# Power_Circuitry.net
KiCad netlist of a schematic drawn in Altium Designer
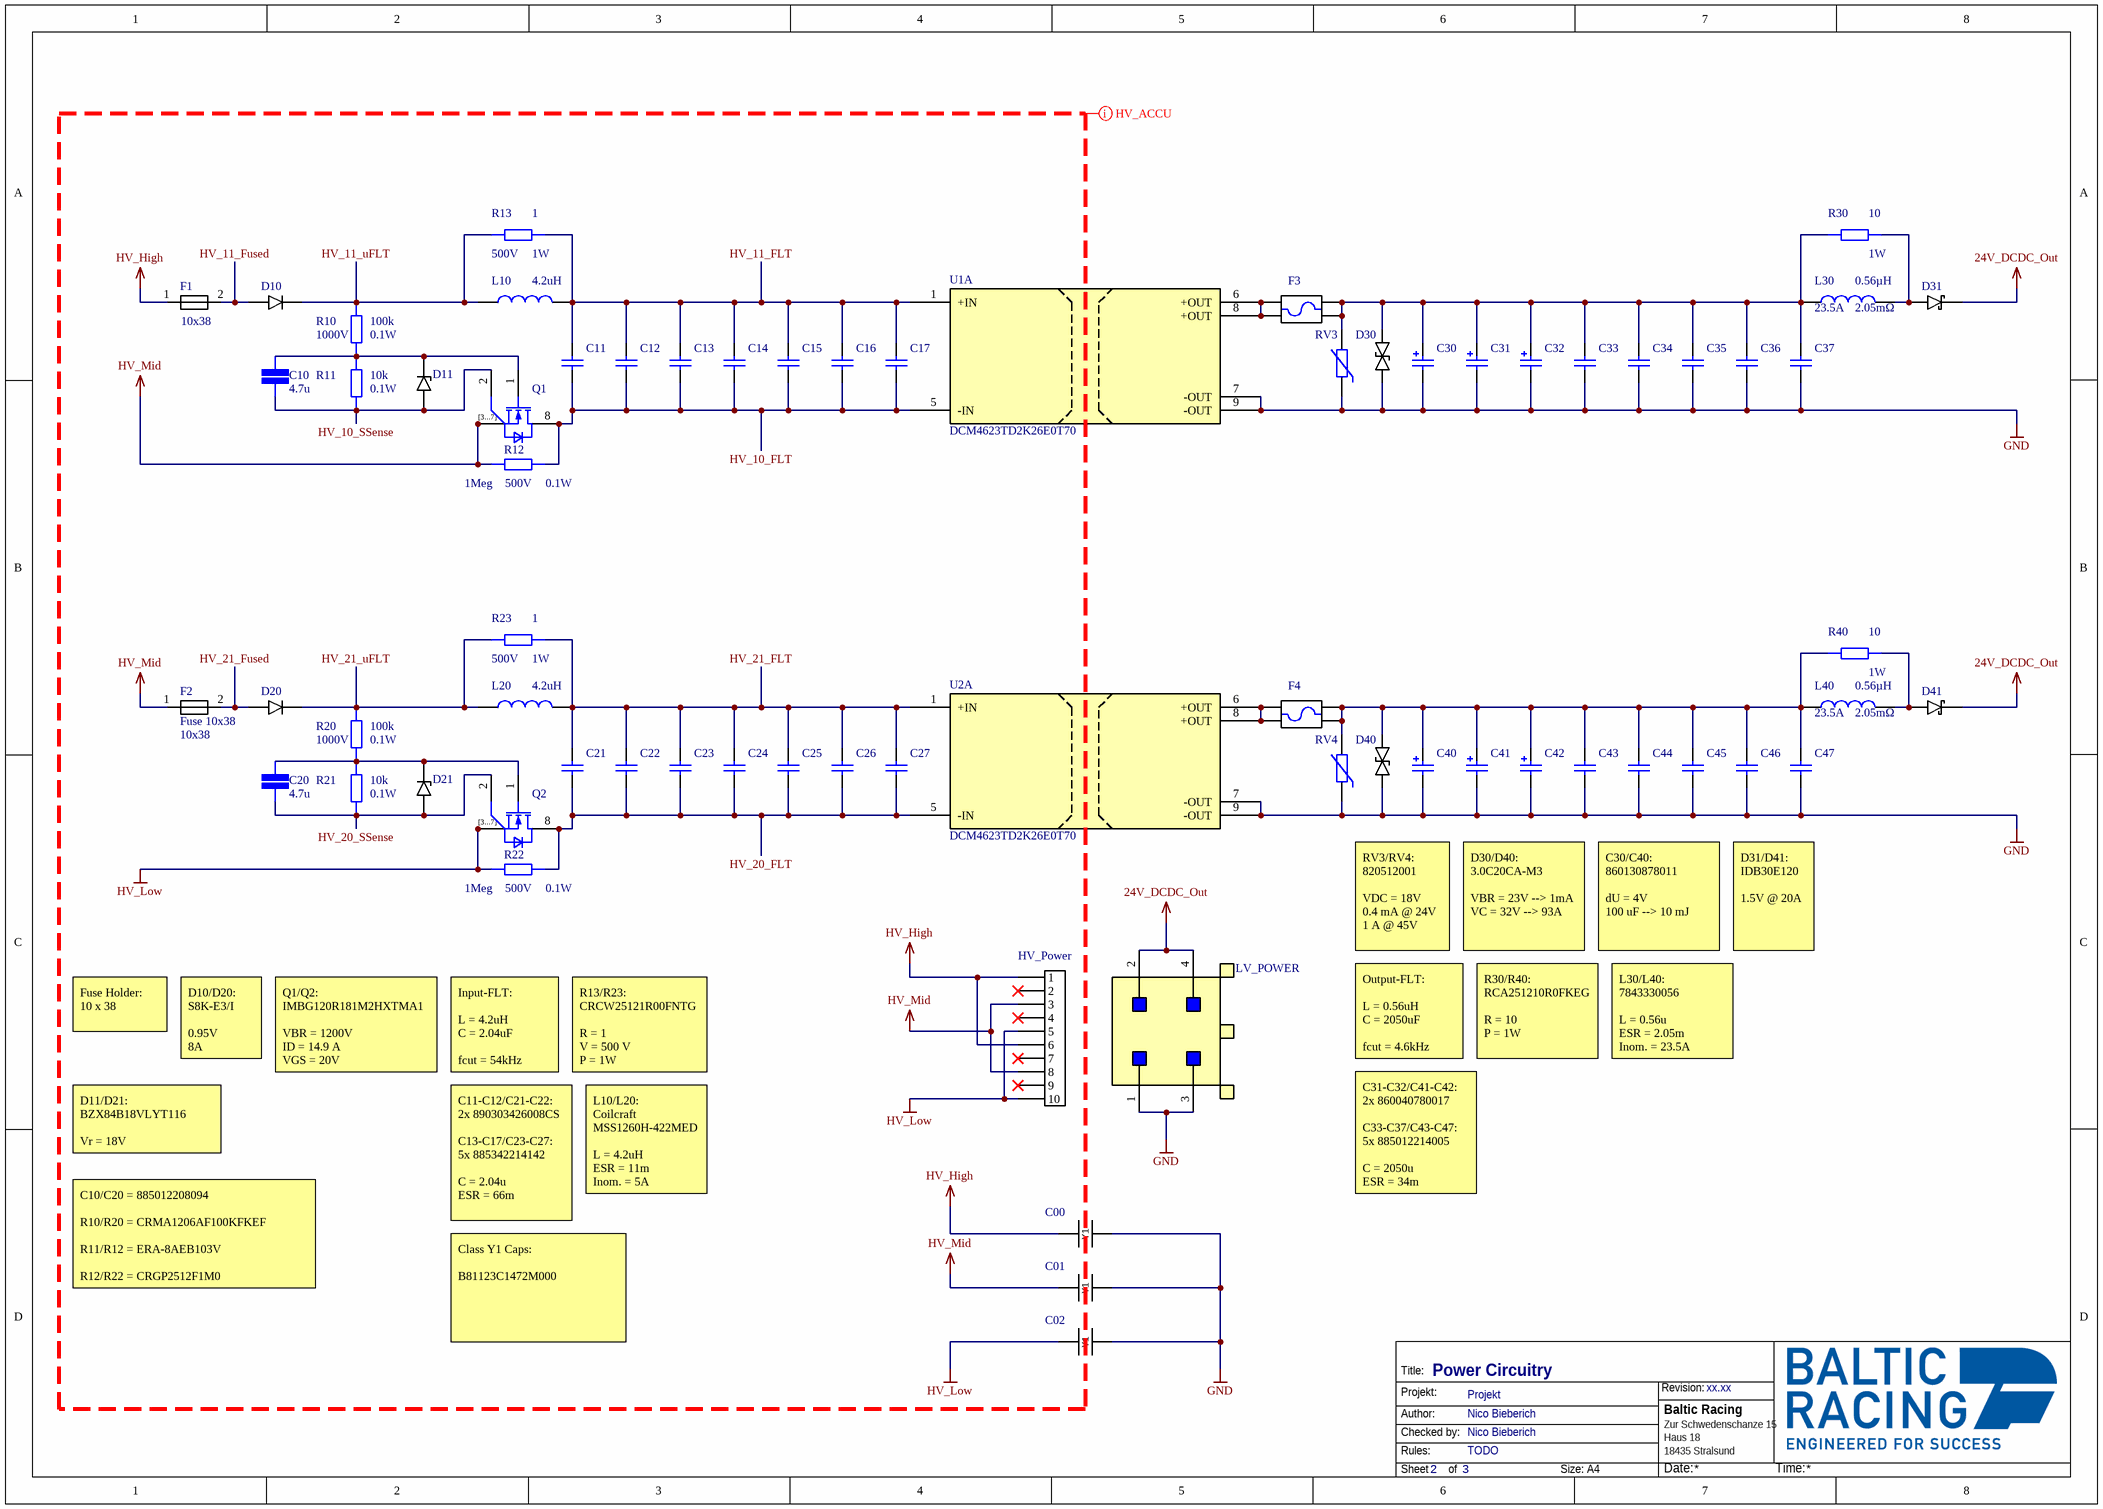
[diagram p0: Power_Circuitry.SchDoc]

(export (version "E")
  (design (tool "Eeschema 10.0.6"))
  (components
    (comp (ref "C00")
      (value "B81123C1472M000")
      (footprint "B81123C1472M000")
      (description "EPCOS/TDK B81123C1472M000\r\nClass Y1 Capacitor")
      (libsource (lib "libNico") (part "B81123C1472M000"))
    )
    (comp (ref "C01")
      (value "B81123C1472M000")
      (footprint "B81123C1472M000")
      (description "EPCOS/TDK B81123C1472M000\r\nClass Y1 Capacitor")
      (libsource (lib "libNico") (part "B81123C1472M000"))
    )
    (comp (ref "C02")
      (value "B81123C1472M000")
      (footprint "B81123C1472M000")
      (description "EPCOS/TDK B81123C1472M000\r\nClass Y1 Capacitor")
      (libsource (lib "libNico") (part "B81123C1472M000"))
    )
    (comp (ref "C10")
      (value "4.7u")
      (footprint "CAP 1206/3216")
      (description "Capacitor with multiple Footprints")
      (fields (field (name "VOLTAGE") "32V") (field (name "Comment") "SMD Capacitor"))
      (libsource (lib "Standardbauteile") (part "SMD Capacitor"))
    )
    (comp (ref "C11")
      (value "630V DC, 0.47 uF")
      (footprint "WCAP-FTBE_26x9x18")
      (description "WCAP-FTBE Film Capacitors, 26x9x18mm, 630V DC, 0.47 uF")
      (fields (field (name "PART NUMBER") "890303426008CS") (field (name "PUBLISHER") "Wurth Elektronik"))
      (libsource (lib "ALTIUM-WCAP-FTBE-rev17a") (part "890303426008CS"))
    )
    (comp (ref "C12")
      (value "630V DC, 0.47 uF")
      (footprint "WCAP-FTBE_26x9x18")
      (description "WCAP-FTBE Film Capacitors, 26x9x18mm, 630V DC, 0.47 uF")
      (fields (field (name "PART NUMBER") "890303426008CS") (field (name "PUBLISHER") "Wurth Elektronik"))
      (libsource (lib "ALTIUM-WCAP-FTBE-rev17a") (part "890303426008CS"))
    )
    (comp (ref "C13")
      (value "220nF")
      (footprint "WCAP-CSMH_2220_L5.7W5H2")
      (fields
        (field (name "MANUFACTURER PART NUMBER") "885342214142")
        (field (name "MANUFACTURER") "Wurth Elektronik")
      )
      (libsource (lib "Altium_WCAP-CSMH (rev22d)") (part "885342214142"))
    )
    (comp (ref "C14")
      (value "220nF")
      (footprint "WCAP-CSMH_2220_L5.7W5H2")
      (fields
        (field (name "MANUFACTURER PART NUMBER") "885342214142")
        (field (name "MANUFACTURER") "Wurth Elektronik")
      )
      (libsource (lib "Altium_WCAP-CSMH (rev22d)") (part "885342214142"))
    )
    (comp (ref "C15")
      (value "220nF")
      (footprint "WCAP-CSMH_2220_L5.7W5H2")
      (fields
        (field (name "MANUFACTURER PART NUMBER") "885342214142")
        (field (name "MANUFACTURER") "Wurth Elektronik")
      )
      (libsource (lib "Altium_WCAP-CSMH (rev22d)") (part "885342214142"))
    )
    (comp (ref "C16")
      (value "220nF")
      (footprint "WCAP-CSMH_2220_L5.7W5H2")
      (fields
        (field (name "MANUFACTURER PART NUMBER") "885342214142")
        (field (name "MANUFACTURER") "Wurth Elektronik")
      )
      (libsource (lib "Altium_WCAP-CSMH (rev22d)") (part "885342214142"))
    )
    (comp (ref "C17")
      (value "220nF")
      (footprint "WCAP-CSMH_2220_L5.7W5H2")
      (fields
        (field (name "MANUFACTURER PART NUMBER") "885342214142")
        (field (name "MANUFACTURER") "Wurth Elektronik")
      )
      (libsource (lib "Altium_WCAP-CSMH (rev22d)") (part "885342214142"))
    )
    (comp (ref "C20")
      (value "4.7u")
      (footprint "CAP 1206/3216")
      (description "Capacitor with multiple Footprints")
      (fields (field (name "VOLTAGE") "32V") (field (name "Comment") "SMD Capacitor"))
      (libsource (lib "Standardbauteile") (part "SMD Capacitor"))
    )
    (comp (ref "C21")
      (value "630V DC, 0.47 uF")
      (footprint "WCAP-FTBE_26x9x18")
      (description "WCAP-FTBE Film Capacitors, 26x9x18mm, 630V DC, 0.47 uF")
      (fields (field (name "PART NUMBER") "890303426008CS") (field (name "PUBLISHER") "Wurth Elektronik"))
      (libsource (lib "ALTIUM-WCAP-FTBE-rev17a") (part "890303426008CS"))
    )
    (comp (ref "C22")
      (value "630V DC, 0.47 uF")
      (footprint "WCAP-FTBE_26x9x18")
      (description "WCAP-FTBE Film Capacitors, 26x9x18mm, 630V DC, 0.47 uF")
      (fields (field (name "PART NUMBER") "890303426008CS") (field (name "PUBLISHER") "Wurth Elektronik"))
      (libsource (lib "ALTIUM-WCAP-FTBE-rev17a") (part "890303426008CS"))
    )
    (comp (ref "C23")
      (value "220nF")
      (footprint "WCAP-CSMH_2220_L5.7W5H2")
      (fields
        (field (name "MANUFACTURER PART NUMBER") "885342214142")
        (field (name "MANUFACTURER") "Wurth Elektronik")
      )
      (libsource (lib "Altium_WCAP-CSMH (rev22d)") (part "885342214142"))
    )
    (comp (ref "C24")
      (value "220nF")
      (footprint "WCAP-CSMH_2220_L5.7W5H2")
      (fields
        (field (name "MANUFACTURER PART NUMBER") "885342214142")
        (field (name "MANUFACTURER") "Wurth Elektronik")
      )
      (libsource (lib "Altium_WCAP-CSMH (rev22d)") (part "885342214142"))
    )
    (comp (ref "C25")
      (value "220nF")
      (footprint "WCAP-CSMH_2220_L5.7W5H2")
      (fields
        (field (name "MANUFACTURER PART NUMBER") "885342214142")
        (field (name "MANUFACTURER") "Wurth Elektronik")
      )
      (libsource (lib "Altium_WCAP-CSMH (rev22d)") (part "885342214142"))
    )
    (comp (ref "C26")
      (value "220nF")
      (footprint "WCAP-CSMH_2220_L5.7W5H2")
      (fields
        (field (name "MANUFACTURER PART NUMBER") "885342214142")
        (field (name "MANUFACTURER") "Wurth Elektronik")
      )
      (libsource (lib "Altium_WCAP-CSMH (rev22d)") (part "885342214142"))
    )
    (comp (ref "C27")
      (value "220nF")
      (footprint "WCAP-CSMH_2220_L5.7W5H2")
      (fields
        (field (name "MANUFACTURER PART NUMBER") "885342214142")
        (field (name "MANUFACTURER") "Wurth Elektronik")
      )
      (libsource (lib "Altium_WCAP-CSMH (rev22d)") (part "885342214142"))
    )
    (comp (ref "C30")
      (value "100uF, 100V")
      (footprint "WCAP-ATET_13x25")
      (description "WCAP-ATET THT Aluminum Electrolytic Capacitors, D13mm x L25mm, 100uF, +/-20%, 100VDC")
      (fields (field (name "PART NUMBER") "860130878011") (field (name "PUBLISHER") "Wurth Elektronik"))
      (libsource (lib "Altium_WCAP-ATET (rev19a)") (part "860130878011"))
    )
    (comp (ref "C31")
      (value "1000uF, 63V")
      (footprint "WCAP-ATUL_16x35.5")
      (description "WCAP-ATUL THT Aluminum Electrolytic Capacitors, D16mm x L35.5mm, 1000uF, +/-20%, 63VDC")
      (fields (field (name "PART NUMBER") "860040780017") (field (name "PUBLISHER") "Wurth Elektronik"))
      (libsource (lib "Altium_WCAP-ATUL_rev19a") (part "860040780017"))
    )
    (comp (ref "C32")
      (value "1000uF, 63V")
      (footprint "WCAP-ATUL_16x35.5")
      (description "WCAP-ATUL THT Aluminum Electrolytic Capacitors, D16mm x L35.5mm, 1000uF, +/-20%, 63VDC")
      (fields (field (name "PART NUMBER") "860040780017") (field (name "PUBLISHER") "Wurth Elektronik"))
      (libsource (lib "Altium_WCAP-ATUL_rev19a") (part "860040780017"))
    )
    (comp (ref "C33")
      (value "10uF")
      (footprint "WCAP-CSGP_2220_L5.7W5H2.8")
      (description "WCAP-CSGP Multilayer Ceramic Chip Capacitor, General Purpose, size 2220, X7R Class II, 10uF, 50VDC")
      (fields
        (field (name "MANUFACTURER PART NUMBER") "885012214005")
        (field (name "MANUFACTURER") "Wurth Elektronik")
      )
      (libsource (lib "Altium_WCAP-CSGP (rev24b)") (part "885012214005"))
    )
    (comp (ref "C34")
      (value "10uF")
      (footprint "WCAP-CSGP_2220_L5.7W5H2.8")
      (description "WCAP-CSGP Multilayer Ceramic Chip Capacitor, General Purpose, size 2220, X7R Class II, 10uF, 50VDC")
      (fields
        (field (name "MANUFACTURER PART NUMBER") "885012214005")
        (field (name "MANUFACTURER") "Wurth Elektronik")
      )
      (libsource (lib "Altium_WCAP-CSGP (rev24b)") (part "885012214005"))
    )
    (comp (ref "C35")
      (value "10uF")
      (footprint "WCAP-CSGP_2220_L5.7W5H2.8")
      (description "WCAP-CSGP Multilayer Ceramic Chip Capacitor, General Purpose, size 2220, X7R Class II, 10uF, 50VDC")
      (fields
        (field (name "MANUFACTURER PART NUMBER") "885012214005")
        (field (name "MANUFACTURER") "Wurth Elektronik")
      )
      (libsource (lib "Altium_WCAP-CSGP (rev24b)") (part "885012214005"))
    )
    (comp (ref "C36")
      (value "10uF")
      (footprint "WCAP-CSGP_2220_L5.7W5H2.8")
      (description "WCAP-CSGP Multilayer Ceramic Chip Capacitor, General Purpose, size 2220, X7R Class II, 10uF, 50VDC")
      (fields
        (field (name "MANUFACTURER PART NUMBER") "885012214005")
        (field (name "MANUFACTURER") "Wurth Elektronik")
      )
      (libsource (lib "Altium_WCAP-CSGP (rev24b)") (part "885012214005"))
    )
    (comp (ref "C37")
      (value "10uF")
      (footprint "WCAP-CSGP_2220_L5.7W5H2.8")
      (description "WCAP-CSGP Multilayer Ceramic Chip Capacitor, General Purpose, size 2220, X7R Class II, 10uF, 50VDC")
      (fields
        (field (name "MANUFACTURER PART NUMBER") "885012214005")
        (field (name "MANUFACTURER") "Wurth Elektronik")
      )
      (libsource (lib "Altium_WCAP-CSGP (rev24b)") (part "885012214005"))
    )
    (comp (ref "C40")
      (value "100uF, 100V")
      (footprint "WCAP-ATET_13x25")
      (description "WCAP-ATET THT Aluminum Electrolytic Capacitors, D13mm x L25mm, 100uF, +/-20%, 100VDC")
      (fields (field (name "PART NUMBER") "860130878011") (field (name "PUBLISHER") "Wurth Elektronik"))
      (libsource (lib "Altium_WCAP-ATET (rev19a)") (part "860130878011"))
    )
    (comp (ref "C41")
      (value "1000uF, 63V")
      (footprint "WCAP-ATUL_16x35.5")
      (description "WCAP-ATUL THT Aluminum Electrolytic Capacitors, D16mm x L35.5mm, 1000uF, +/-20%, 63VDC")
      (fields (field (name "PART NUMBER") "860040780017") (field (name "PUBLISHER") "Wurth Elektronik"))
      (libsource (lib "Altium_WCAP-ATUL_rev19a") (part "860040780017"))
    )
    (comp (ref "C42")
      (value "1000uF, 63V")
      (footprint "WCAP-ATUL_16x35.5")
      (description "WCAP-ATUL THT Aluminum Electrolytic Capacitors, D16mm x L35.5mm, 1000uF, +/-20%, 63VDC")
      (fields (field (name "PART NUMBER") "860040780017") (field (name "PUBLISHER") "Wurth Elektronik"))
      (libsource (lib "Altium_WCAP-ATUL_rev19a") (part "860040780017"))
    )
    (comp (ref "C43")
      (value "10uF")
      (footprint "WCAP-CSGP_2220_L5.7W5H2.8")
      (description "WCAP-CSGP Multilayer Ceramic Chip Capacitor, General Purpose, size 2220, X7R Class II, 10uF, 50VDC")
      (fields
        (field (name "MANUFACTURER PART NUMBER") "885012214005")
        (field (name "MANUFACTURER") "Wurth Elektronik")
      )
      (libsource (lib "Altium_WCAP-CSGP (rev24b)") (part "885012214005"))
    )
    (comp (ref "C44")
      (value "10uF")
      (footprint "WCAP-CSGP_2220_L5.7W5H2.8")
      (description "WCAP-CSGP Multilayer Ceramic Chip Capacitor, General Purpose, size 2220, X7R Class II, 10uF, 50VDC")
      (fields
        (field (name "MANUFACTURER PART NUMBER") "885012214005")
        (field (name "MANUFACTURER") "Wurth Elektronik")
      )
      (libsource (lib "Altium_WCAP-CSGP (rev24b)") (part "885012214005"))
    )
    (comp (ref "C45")
      (value "10uF")
      (footprint "WCAP-CSGP_2220_L5.7W5H2.8")
      (description "WCAP-CSGP Multilayer Ceramic Chip Capacitor, General Purpose, size 2220, X7R Class II, 10uF, 50VDC")
      (fields
        (field (name "MANUFACTURER PART NUMBER") "885012214005")
        (field (name "MANUFACTURER") "Wurth Elektronik")
      )
      (libsource (lib "Altium_WCAP-CSGP (rev24b)") (part "885012214005"))
    )
    (comp (ref "C46")
      (value "10uF")
      (footprint "WCAP-CSGP_2220_L5.7W5H2.8")
      (description "WCAP-CSGP Multilayer Ceramic Chip Capacitor, General Purpose, size 2220, X7R Class II, 10uF, 50VDC")
      (fields
        (field (name "MANUFACTURER PART NUMBER") "885012214005")
        (field (name "MANUFACTURER") "Wurth Elektronik")
      )
      (libsource (lib "Altium_WCAP-CSGP (rev24b)") (part "885012214005"))
    )
    (comp (ref "C47")
      (value "10uF")
      (footprint "WCAP-CSGP_2220_L5.7W5H2.8")
      (description "WCAP-CSGP Multilayer Ceramic Chip Capacitor, General Purpose, size 2220, X7R Class II, 10uF, 50VDC")
      (fields
        (field (name "MANUFACTURER PART NUMBER") "885012214005")
        (field (name "MANUFACTURER") "Wurth Elektronik")
      )
      (libsource (lib "Altium_WCAP-CSGP (rev24b)") (part "885012214005"))
    )
    (comp (ref "D10")
      (value "S8K-E3/I")
      (footprint "S8K-E3/I")
      (description "Vishay S8K-E3/I\r\nDiode, 950mV, 8A, 800V")
      (libsource (lib "libNico") (part "S8K-E3/I"))
    )
    (comp (ref "D11")
      (value "BZX84B18VLYT116")
      (footprint "SOT-23-3")
      (description "ROHM BZX84B18VLYT116\r\nZ-Diode, 18V")
      (libsource (lib "libNico") (part "BZX84B18VLYT116"))
    )
    (comp (ref "D20")
      (value "S8K-E3/I")
      (footprint "S8K-E3/I")
      (description "Vishay S8K-E3/I\r\nDiode, 950mV, 8A, 800V")
      (libsource (lib "libNico") (part "S8K-E3/I"))
    )
    (comp (ref "D21")
      (value "BZX84B18VLYT116")
      (footprint "SOT-23-3")
      (description "ROHM BZX84B18VLYT116\r\nZ-Diode, 18V")
      (libsource (lib "libNico") (part "BZX84B18VLYT116"))
    )
    (comp (ref "D30")
      (value "3.0C20CA-M3")
      (footprint "3.0C20CA-M3")
      (description "Vishay 3.0C20CA-M3\r\nBidirect. TVS, 20V, 3kW")
      (libsource (lib "libNico") (part "3.0C20CA-M3"))
    )
    (comp (ref "D31")
      (value "IDB30E120")
      (footprint "Infineon IDB30E120")
      (description "Infineon IDB30E120\r\n1200V, 30A @ 1.7V")
      (libsource (lib "libNico") (part "IDB30E120"))
    )
    (comp (ref "D40")
      (value "3.0C20CA-M3")
      (footprint "3.0C20CA-M3")
      (description "Vishay 3.0C20CA-M3\r\nBidirect. TVS, 20V, 3kW")
      (libsource (lib "libNico") (part "3.0C20CA-M3"))
    )
    (comp (ref "D41")
      (value "IDB30E120")
      (footprint "Infineon IDB30E120")
      (description "Infineon IDB30E120\r\n1200V, 30A @ 1.7V")
      (libsource (lib "libNico") (part "IDB30E120"))
    )
    (comp (ref "F1")
      (value "Fuse 10x38")
      (footprint "Fuse Holder 10x38")
      (fields (field (name "FORMAT") "10x38"))
      (libsource (lib "libNico") (part "Fuse 10x38"))
    )
    (comp (ref "F2")
      (value "Fuse 10x38")
      (footprint "Fuse Holder 10x38")
      (fields (field (name "FORMAT") "10x38"))
      (libsource (lib "libNico") (part "Fuse 10x38"))
    )
    (comp (ref "F3")
      (value "Keystone 3557-2")
      (footprint "Keystone 3557-2")
      (description "Keystone 3557-2\r\nFuse Holder")
      (libsource (lib "libNico") (part "Keystone 3557-2"))
    )
    (comp (ref "F4")
      (value "Keystone 3557-2")
      (footprint "Keystone 3557-2")
      (description "Keystone 3557-2\r\nFuse Holder")
      (libsource (lib "libNico") (part "Keystone 3557-2"))
    )
    (comp (ref "HV_Power")
      (value "43045-1012")
      (footprint "43045-1012")
      (libsource (lib "molex_43045") (part "43045-1012"))
    )
    (comp (ref "L10")
      (value "4.2uH")
      (footprint "Coilcraft MSS1260H-422MED")
      (description "Coilcraft MSS1260H-422MED\r\nShielded Inductor, 4.2uH, 11mOhm, 5A")
      (fields (field (name "Comment") "MSS1260H-422MED"))
      (libsource (lib "libNico") (part "MSS1260H-422MED"))
    )
    (comp (ref "L20")
      (value "4.2uH")
      (footprint "Coilcraft MSS1260H-422MED")
      (description "Coilcraft MSS1260H-422MED\r\nShielded Inductor, 4.2uH, 11mOhm, 5A")
      (fields (field (name "Comment") "MSS1260H-422MED"))
      (libsource (lib "libNico") (part "MSS1260H-422MED"))
    )
    (comp (ref "L30")
      (value "0.56µH, 23.5A")
      (footprint "WE-CHSA_1011")
      (description "WE-CHSA SMT High Current Inductor, size 1011, 0.56µH, 23.5A, 2.05mΩ")
      (fields
        (field (name "MANUFACTURER PART NUMBER") "7843330056")
        (field (name "MANUFACTURER") "Wurth Elektronik")
        (field (name "DC RESISTANCE MAX") "2.05mΩ")
        (field (name "INDUCTANCE") "0.56µH")
        (field (name "RATED CURRENT") "23.5A")
      )
      (libsource (lib "Altium_WE-CHSA (rev22d)") (part "7843330056"))
    )
    (comp (ref "L40")
      (value "0.56µH, 23.5A")
      (footprint "WE-CHSA_1011")
      (description "WE-CHSA SMT High Current Inductor, size 1011, 0.56µH, 23.5A, 2.05mΩ")
      (fields
        (field (name "MANUFACTURER PART NUMBER") "7843330056")
        (field (name "MANUFACTURER") "Wurth Elektronik")
        (field (name "DC RESISTANCE MAX") "2.05mΩ")
        (field (name "INDUCTANCE") "0.56µH")
        (field (name "RATED CURRENT") "23.5A")
      )
      (libsource (lib "Altium_WE-CHSA (rev22d)") (part "7843330056"))
    )
    (comp (ref "LV_POWER")
      (value "1720650004")
      (footprint "1720650004")
      (libsource (lib "libNico") (part "1720650004"))
    )
    (comp (ref "Q1")
      (value "IMBG120R181M2H")
      (footprint "TO127P1500X470-8N-2-V1")
      (description "Infineon IMBG120R181M2HXTMA1\r\nCoolSiC, 1200V, 15A, 181.4mOhm")
      (libsource (lib "libNico") (part "IMBG120R181M2H"))
    )
    (comp (ref "Q2")
      (value "IMBG120R181M2H")
      (footprint "TO127P1500X470-8N-2-V1")
      (description "Infineon IMBG120R181M2HXTMA1\r\nCoolSiC, 1200V, 15A, 181.4mOhm")
      (libsource (lib "libNico") (part "IMBG120R181M2H"))
    )
    (comp (ref "R10")
      (value "100k")
      (footprint "STACKPOLE CSR1206")
      (description "Resistor with multiple footprints")
      (fields
        (field (name "VOLTAGE") "1000V")
        (field (name "POWER") "0.1W")
        (field (name "Comment") "SMD Resistor")
      )
      (libsource (lib "Standardbauteile") (part "SMD Resistor"))
    )
    (comp (ref "R11")
      (value "10k")
      (footprint "STACKPOLE CSR1206")
      (description "Resistor with multiple footprints")
      (fields
        (field (name "VOLTAGE") "1000V")
        (field (name "POWER") "0.1W")
        (field (name "Comment") "SMD Resistor")
      )
      (libsource (lib "Standardbauteile") (part "SMD Resistor"))
    )
    (comp (ref "R12")
      (value "1Meg")
      (footprint "STACKPOLE CSRN2512")
      (description "Resistor with multiple footprints")
      (fields
        (field (name "VOLTAGE") "500V")
        (field (name "POWER") "0.1W")
        (field (name "Comment") "SMD Resistor")
      )
      (libsource (lib "Standardbauteile") (part "SMD Resistor"))
    )
    (comp (ref "R13")
      (value "1")
      (footprint "STACKPOLE CSRN2512")
      (description "Resistor with multiple footprints")
      (fields
        (field (name "VOLTAGE") "500V")
        (field (name "POWER") "1W")
        (field (name "Comment") "SMD Resistor")
      )
      (libsource (lib "Standardbauteile") (part "SMD Resistor"))
    )
    (comp (ref "R20")
      (value "100k")
      (footprint "STACKPOLE CSR1206")
      (description "Resistor with multiple footprints")
      (fields
        (field (name "VOLTAGE") "1000V")
        (field (name "POWER") "0.1W")
        (field (name "Comment") "SMD Resistor")
      )
      (libsource (lib "Standardbauteile") (part "SMD Resistor"))
    )
    (comp (ref "R21")
      (value "10k")
      (footprint "STACKPOLE CSR1206")
      (description "Resistor with multiple footprints")
      (fields
        (field (name "VOLTAGE") "1000V")
        (field (name "POWER") "0.1W")
        (field (name "Comment") "SMD Resistor")
      )
      (libsource (lib "Standardbauteile") (part "SMD Resistor"))
    )
    (comp (ref "R22")
      (value "1Meg")
      (footprint "STACKPOLE CSRN2512")
      (description "Resistor with multiple footprints")
      (fields
        (field (name "VOLTAGE") "500V")
        (field (name "POWER") "0.1W")
        (field (name "Comment") "SMD Resistor")
      )
      (libsource (lib "Standardbauteile") (part "SMD Resistor"))
    )
    (comp (ref "R23")
      (value "1")
      (footprint "STACKPOLE CSRN2512")
      (description "Resistor with multiple footprints")
      (fields
        (field (name "VOLTAGE") "500V")
        (field (name "POWER") "1W")
        (field (name "Comment") "SMD Resistor")
      )
      (libsource (lib "Standardbauteile") (part "SMD Resistor"))
    )
    (comp (ref "R30")
      (value "10")
      (footprint "STACKPOLE CSRN2512")
      (description "Resistor with multiple footprints")
      (fields (field (name "POWER") "1W") (field (name "Comment") "SMD Resistor"))
      (libsource (lib "Standardbauteile") (part "SMD Resistor"))
    )
    (comp (ref "R40")
      (value "10")
      (footprint "STACKPOLE CSRN2512")
      (description "Resistor with multiple footprints")
      (fields (field (name "POWER") "1W") (field (name "Comment") "SMD Resistor"))
      (libsource (lib "Standardbauteile") (part "SMD Resistor"))
    )
    (comp (ref "RV3")
      (value "20VAC, 26VDC")
      (footprint "D12.5W5.1H15.5P0.8")
      (description "WE-VD Disk Varistor, THT, 20VAC, 26VDC, 4250pF")
      (fields
        (field (name "MANUFACTURER PART NUMBER") "820512001")
        (field (name "MANUFACTURER") "Wurth Elektronik")
      )
      (libsource (lib "Altium_WE-VD (rev23a)") (part "820512001"))
    )
    (comp (ref "RV4")
      (value "20VAC, 26VDC")
      (footprint "D12.5W5.1H15.5P0.8")
      (description "WE-VD Disk Varistor, THT, 20VAC, 26VDC, 4250pF")
      (fields
        (field (name "MANUFACTURER PART NUMBER") "820512001")
        (field (name "MANUFACTURER") "Wurth Elektronik")
      )
      (libsource (lib "Altium_WE-VD (rev23a)") (part "820512001"))
    )
    (comp (ref "U1")
      (value "DCM4623")
      (footprint "DCM4623")
      (description "VICOR DCM® DC-DC Converter Module")
      (fields (field (name "MODEL") "DCM4623TD2K26E0T70"))
      (libsource (lib "libNico") (part "DCM4623"))
    )
    (comp (ref "U2")
      (value "DCM4623")
      (footprint "DCM4623")
      (description "VICOR DCM® DC-DC Converter Module")
      (fields (field (name "MODEL") "DCM4623TD2K26E0T70"))
      (libsource (lib "libNico") (part "DCM4623"))
    )
  )
  (nets
    (net (code "1") (name "/HV_10_FLT") (class "Default")
      (node (ref "C11") (pin "1") (pinfunction "1_1") (pintype "passive"))
      (node (ref "C12") (pin "1") (pinfunction "1_1") (pintype "passive"))
      (node (ref "C13") (pin "1") (pinfunction "1_1") (pintype "passive"))
      (node (ref "C14") (pin "1") (pinfunction "1_1") (pintype "passive"))
      (node (ref "C15") (pin "1") (pinfunction "1_1") (pintype "passive"))
      (node (ref "C16") (pin "1") (pinfunction "1_1") (pintype "passive"))
      (node (ref "C17") (pin "1") (pinfunction "1_1") (pintype "passive"))
      (node (ref "Q1") (pin "8") (pinfunction "DRAIN_8") (pintype "passive"))
      (node (ref "R12") (pin "1") (pinfunction "1_1") (pintype "passive"))
      (node (ref "U1") (pin "5") (pinfunction "-IN_5") (pintype "passive"))
    )
    (net (code "2") (name "/HV_10_SSense") (class "Default")
      (node (ref "C10") (pin "1") (pinfunction "1_1") (pintype "passive"))
      (node (ref "D11") (pin "1") (pinfunction "A_1") (pintype "passive"))
      (node (ref "Q1") (pin "2") (pinfunction "SENSE_2") (pintype "passive"))
      (node (ref "R11") (pin "1") (pinfunction "1_1") (pintype "passive"))
    )
    (net (code "3") (name "/HV_11_FLT") (class "Default")
      (node (ref "C11") (pin "2") (pinfunction "2_2") (pintype "passive"))
      (node (ref "C12") (pin "2") (pinfunction "2_2") (pintype "passive"))
      (node (ref "C13") (pin "2") (pinfunction "2_2") (pintype "passive"))
      (node (ref "C14") (pin "2") (pinfunction "2_2") (pintype "passive"))
      (node (ref "C15") (pin "2") (pinfunction "2_2") (pintype "passive"))
      (node (ref "C16") (pin "2") (pinfunction "2_2") (pintype "passive"))
      (node (ref "C17") (pin "2") (pinfunction "2_2") (pintype "passive"))
      (node (ref "L10") (pin "2") (pinfunction "2_2") (pintype "passive"))
      (node (ref "R13") (pin "1") (pinfunction "1_1") (pintype "passive"))
      (node (ref "U1") (pin "1") (pinfunction "+IN_1") (pintype "power_in"))
    )
    (net (code "4") (name "/HV_11_Fused") (class "Default")
      (node (ref "D10") (pin "2") (pinfunction "A_2") (pintype "passive"))
      (node (ref "F1") (pin "2") (pinfunction "2_2") (pintype "passive"))
    )
    (net (code "5") (name "/HV_11_uFLT") (class "Default")
      (node (ref "D10") (pin "1") (pinfunction "C_1") (pintype "passive"))
      (node (ref "L10") (pin "1") (pinfunction "1_1") (pintype "passive"))
      (node (ref "R10") (pin "2") (pinfunction "2_2") (pintype "passive"))
      (node (ref "R13") (pin "2") (pinfunction "2_2") (pintype "passive"))
    )
    (net (code "6") (name "/HV_20_FLT") (class "Default")
      (node (ref "C21") (pin "1") (pinfunction "1_1") (pintype "passive"))
      (node (ref "C22") (pin "1") (pinfunction "1_1") (pintype "passive"))
      (node (ref "C23") (pin "1") (pinfunction "1_1") (pintype "passive"))
      (node (ref "C24") (pin "1") (pinfunction "1_1") (pintype "passive"))
      (node (ref "C25") (pin "1") (pinfunction "1_1") (pintype "passive"))
      (node (ref "C26") (pin "1") (pinfunction "1_1") (pintype "passive"))
      (node (ref "C27") (pin "1") (pinfunction "1_1") (pintype "passive"))
      (node (ref "Q2") (pin "8") (pinfunction "DRAIN_8") (pintype "passive"))
      (node (ref "R22") (pin "1") (pinfunction "1_1") (pintype "passive"))
      (node (ref "U2") (pin "5") (pinfunction "-IN_5") (pintype "passive"))
    )
    (net (code "7") (name "/HV_20_SSense") (class "Default")
      (node (ref "C20") (pin "1") (pinfunction "1_1") (pintype "passive"))
      (node (ref "D21") (pin "1") (pinfunction "A_1") (pintype "passive"))
      (node (ref "Q2") (pin "2") (pinfunction "SENSE_2") (pintype "passive"))
      (node (ref "R21") (pin "1") (pinfunction "1_1") (pintype "passive"))
    )
    (net (code "8") (name "/HV_21_FLT") (class "Default")
      (node (ref "C21") (pin "2") (pinfunction "2_2") (pintype "passive"))
      (node (ref "C22") (pin "2") (pinfunction "2_2") (pintype "passive"))
      (node (ref "C23") (pin "2") (pinfunction "2_2") (pintype "passive"))
      (node (ref "C24") (pin "2") (pinfunction "2_2") (pintype "passive"))
      (node (ref "C25") (pin "2") (pinfunction "2_2") (pintype "passive"))
      (node (ref "C26") (pin "2") (pinfunction "2_2") (pintype "passive"))
      (node (ref "C27") (pin "2") (pinfunction "2_2") (pintype "passive"))
      (node (ref "L20") (pin "2") (pinfunction "2_2") (pintype "passive"))
      (node (ref "R23") (pin "1") (pinfunction "1_1") (pintype "passive"))
      (node (ref "U2") (pin "1") (pinfunction "+IN_1") (pintype "power_in"))
    )
    (net (code "9") (name "/HV_21_Fused") (class "Default")
      (node (ref "D20") (pin "2") (pinfunction "A_2") (pintype "passive"))
      (node (ref "F2") (pin "2") (pinfunction "2_2") (pintype "passive"))
    )
    (net (code "10") (name "/HV_21_uFLT") (class "Default")
      (node (ref "D20") (pin "1") (pinfunction "C_1") (pintype "passive"))
      (node (ref "L20") (pin "1") (pinfunction "1_1") (pintype "passive"))
      (node (ref "R20") (pin "2") (pinfunction "2_2") (pintype "passive"))
      (node (ref "R23") (pin "2") (pinfunction "2_2") (pintype "passive"))
    )
    (net (code "11") (name "24V_DCDC_Out") (class "Default")
      (node (ref "D31") (pin "2") (pinfunction "C_2") (pintype "passive"))
      (node (ref "D41") (pin "2") (pinfunction "C_2") (pintype "passive"))
      (node (ref "LV_POWER") (pin "2") (pinfunction "2_2") (pintype "passive"))
      (node (ref "LV_POWER") (pin "4") (pinfunction "4_4") (pintype "passive"))
    )
    (net (code "12") (name "GND") (class "Default")
      (node (ref "C00") (pin "2") (pinfunction "2_2") (pintype "passive"))
      (node (ref "C01") (pin "2") (pinfunction "2_2") (pintype "passive"))
      (node (ref "C02") (pin "2") (pinfunction "2_2") (pintype "passive"))
      (node (ref "C30") (pin "1") (pinfunction "N_1") (pintype "passive"))
      (node (ref "C31") (pin "1") (pinfunction "N_1") (pintype "passive"))
      (node (ref "C32") (pin "1") (pinfunction "N_1") (pintype "passive"))
      (node (ref "C33") (pin "1") (pinfunction "1_1") (pintype "passive"))
      (node (ref "C34") (pin "1") (pinfunction "1_1") (pintype "passive"))
      (node (ref "C35") (pin "1") (pinfunction "1_1") (pintype "passive"))
      (node (ref "C36") (pin "1") (pinfunction "1_1") (pintype "passive"))
      (node (ref "C37") (pin "1") (pinfunction "1_1") (pintype "passive"))
      (node (ref "C40") (pin "1") (pinfunction "N_1") (pintype "passive"))
      (node (ref "C41") (pin "1") (pinfunction "N_1") (pintype "passive"))
      (node (ref "C42") (pin "1") (pinfunction "N_1") (pintype "passive"))
      (node (ref "C43") (pin "1") (pinfunction "1_1") (pintype "passive"))
      (node (ref "C44") (pin "1") (pinfunction "1_1") (pintype "passive"))
      (node (ref "C45") (pin "1") (pinfunction "1_1") (pintype "passive"))
      (node (ref "C46") (pin "1") (pinfunction "1_1") (pintype "passive"))
      (node (ref "C47") (pin "1") (pinfunction "1_1") (pintype "passive"))
      (node (ref "D30") (pin "1") (pinfunction "1_1") (pintype "passive"))
      (node (ref "D40") (pin "1") (pinfunction "1_1") (pintype "passive"))
      (node (ref "LV_POWER") (pin "1") (pinfunction "1_1") (pintype "passive"))
      (node (ref "LV_POWER") (pin "3") (pinfunction "3_3") (pintype "passive"))
      (node (ref "RV3") (pin "1") (pinfunction "1_1") (pintype "passive"))
      (node (ref "RV4") (pin "1") (pinfunction "1_1") (pintype "passive"))
      (node (ref "U1") (pin "7") (pinfunction "-OUT_7") (pintype "passive"))
      (node (ref "U1") (pin "9") (pinfunction "-OUT_9") (pintype "passive"))
      (node (ref "U2") (pin "7") (pinfunction "-OUT_7") (pintype "passive"))
      (node (ref "U2") (pin "9") (pinfunction "-OUT_9") (pintype "passive"))
    )
    (net (code "13") (name "HV_High") (class "Default")
      (node (ref "C00") (pin "1") (pinfunction "1_1") (pintype "passive"))
      (node (ref "F1") (pin "1") (pinfunction "1_1") (pintype "passive"))
      (node (ref "HV_Power") (pin "1") (pinfunction "1_1") (pintype "passive"))
      (node (ref "HV_Power") (pin "6") (pinfunction "6_6") (pintype "passive"))
    )
    (net (code "14") (name "HV_Low") (class "Default")
      (node (ref "C02") (pin "1") (pinfunction "1_1") (pintype "passive"))
      (node (ref "HV_Power") (pin "10") (pinfunction "10_10") (pintype "passive"))
      (node (ref "HV_Power") (pin "5") (pinfunction "5_5") (pintype "passive"))
      (node (ref "Q2") (pin "3") (pinfunction "SOURCE1_3") (pintype "passive"))
      (node (ref "Q2") (pin "4") (pinfunction "SOURCE2_4") (pintype "passive"))
      (node (ref "Q2") (pin "5") (pinfunction "SOURCE3_5") (pintype "passive"))
      (node (ref "Q2") (pin "6") (pinfunction "SOURCE4_6") (pintype "passive"))
      (node (ref "Q2") (pin "7") (pinfunction "SOURCE5_7") (pintype "passive"))
      (node (ref "R22") (pin "2") (pinfunction "2_2") (pintype "passive"))
    )
    (net (code "15") (name "HV_Mid") (class "Default")
      (node (ref "C01") (pin "1") (pinfunction "1_1") (pintype "passive"))
      (node (ref "F2") (pin "1") (pinfunction "1_1") (pintype "passive"))
      (node (ref "HV_Power") (pin "3") (pinfunction "3_3") (pintype "passive"))
      (node (ref "HV_Power") (pin "8") (pinfunction "8_8") (pintype "passive"))
      (node (ref "Q1") (pin "3") (pinfunction "SOURCE1_3") (pintype "passive"))
      (node (ref "Q1") (pin "4") (pinfunction "SOURCE2_4") (pintype "passive"))
      (node (ref "Q1") (pin "5") (pinfunction "SOURCE3_5") (pintype "passive"))
      (node (ref "Q1") (pin "6") (pinfunction "SOURCE4_6") (pintype "passive"))
      (node (ref "Q1") (pin "7") (pinfunction "SOURCE5_7") (pintype "passive"))
      (node (ref "R12") (pin "2") (pinfunction "2_2") (pintype "passive"))
    )
    (net (code "16") (name "Net-(C30-P)") (class "Default")
      (node (ref "C30") (pin "2") (pinfunction "P_2") (pintype "passive"))
      (node (ref "C31") (pin "2") (pinfunction "P_2") (pintype "passive"))
      (node (ref "C32") (pin "2") (pinfunction "P_2") (pintype "passive"))
      (node (ref "C33") (pin "2") (pinfunction "2_2") (pintype "passive"))
      (node (ref "C34") (pin "2") (pinfunction "2_2") (pintype "passive"))
      (node (ref "C35") (pin "2") (pinfunction "2_2") (pintype "passive"))
      (node (ref "C36") (pin "2") (pinfunction "2_2") (pintype "passive"))
      (node (ref "C37") (pin "2") (pinfunction "2_2") (pintype "passive"))
      (node (ref "D30") (pin "2") (pinfunction "2_2") (pintype "passive"))
      (node (ref "F3") (pin "O1") (pinfunction "O1_O1") (pintype "passive"))
      (node (ref "F3") (pin "O2") (pinfunction "O2_O2") (pintype "passive"))
      (node (ref "L30") (pin "1") (pinfunction "1_1") (pintype "passive"))
      (node (ref "R30") (pin "2") (pinfunction "2_2") (pintype "passive"))
      (node (ref "RV3") (pin "2") (pinfunction "2_2") (pintype "passive"))
    )
    (net (code "17") (name "Net-(C40-P)") (class "Default")
      (node (ref "C40") (pin "2") (pinfunction "P_2") (pintype "passive"))
      (node (ref "C41") (pin "2") (pinfunction "P_2") (pintype "passive"))
      (node (ref "C42") (pin "2") (pinfunction "P_2") (pintype "passive"))
      (node (ref "C43") (pin "2") (pinfunction "2_2") (pintype "passive"))
      (node (ref "C44") (pin "2") (pinfunction "2_2") (pintype "passive"))
      (node (ref "C45") (pin "2") (pinfunction "2_2") (pintype "passive"))
      (node (ref "C46") (pin "2") (pinfunction "2_2") (pintype "passive"))
      (node (ref "C47") (pin "2") (pinfunction "2_2") (pintype "passive"))
      (node (ref "D40") (pin "2") (pinfunction "2_2") (pintype "passive"))
      (node (ref "F4") (pin "O1") (pinfunction "O1_O1") (pintype "passive"))
      (node (ref "F4") (pin "O2") (pinfunction "O2_O2") (pintype "passive"))
      (node (ref "L40") (pin "1") (pinfunction "1_1") (pintype "passive"))
      (node (ref "R40") (pin "2") (pinfunction "2_2") (pintype "passive"))
      (node (ref "RV4") (pin "2") (pinfunction "2_2") (pintype "passive"))
    )
    (net (code "18") (name "Net-(D11-C)") (class "Default")
      (node (ref "C10") (pin "2") (pinfunction "2_2") (pintype "passive"))
      (node (ref "D11") (pin "3") (pinfunction "C_3") (pintype "passive"))
      (node (ref "Q1") (pin "1") (pinfunction "GATE_1") (pintype "passive"))
      (node (ref "R10") (pin "1") (pinfunction "1_1") (pintype "passive"))
      (node (ref "R11") (pin "2") (pinfunction "2_2") (pintype "passive"))
    )
    (net (code "19") (name "Net-(D21-C)") (class "Default")
      (node (ref "C20") (pin "2") (pinfunction "2_2") (pintype "passive"))
      (node (ref "D21") (pin "3") (pinfunction "C_3") (pintype "passive"))
      (node (ref "Q2") (pin "1") (pinfunction "GATE_1") (pintype "passive"))
      (node (ref "R20") (pin "1") (pinfunction "1_1") (pintype "passive"))
      (node (ref "R21") (pin "2") (pinfunction "2_2") (pintype "passive"))
    )
    (net (code "20") (name "Net-(D31-A)") (class "Default")
      (node (ref "D31") (pin "3") (pinfunction "A_3") (pintype "passive"))
      (node (ref "L30") (pin "2") (pinfunction "2_2") (pintype "passive"))
      (node (ref "R30") (pin "1") (pinfunction "1_1") (pintype "passive"))
    )
    (net (code "21") (name "Net-(D41-A)") (class "Default")
      (node (ref "D41") (pin "3") (pinfunction "A_3") (pintype "passive"))
      (node (ref "L40") (pin "2") (pinfunction "2_2") (pintype "passive"))
      (node (ref "R40") (pin "1") (pinfunction "1_1") (pintype "passive"))
    )
    (net (code "22") (name "Net-(F3-PadI1)") (class "Default")
      (node (ref "F3") (pin "I1") (pinfunction "I1_I1") (pintype "passive"))
      (node (ref "F3") (pin "I2") (pinfunction "I2_I2") (pintype "passive"))
      (node (ref "U1") (pin "6") (pinfunction "+OUT_6") (pintype "power_in"))
      (node (ref "U1") (pin "8") (pinfunction "+OUT_8") (pintype "power_in"))
    )
    (net (code "23") (name "Net-(F4-PadI1)") (class "Default")
      (node (ref "F4") (pin "I1") (pinfunction "I1_I1") (pintype "passive"))
      (node (ref "F4") (pin "I2") (pinfunction "I2_I2") (pintype "passive"))
      (node (ref "U2") (pin "6") (pinfunction "+OUT_6") (pintype "power_in"))
      (node (ref "U2") (pin "8") (pinfunction "+OUT_8") (pintype "power_in"))
    )
    (net (code "24") (name "unconnected-(HV_Power-Pad2)") (class "Default")
      (node (ref "HV_Power") (pin "2") (pinfunction "2_2") (pintype "passive+no_connect"))
    )
    (net (code "25") (name "unconnected-(HV_Power-Pad4)") (class "Default")
      (node (ref "HV_Power") (pin "4") (pinfunction "4_4") (pintype "passive+no_connect"))
    )
    (net (code "26") (name "unconnected-(HV_Power-Pad7)") (class "Default")
      (node (ref "HV_Power") (pin "7") (pinfunction "7_7") (pintype "passive+no_connect"))
    )
    (net (code "27") (name "unconnected-(HV_Power-Pad9)") (class "Default")
      (node (ref "HV_Power") (pin "9") (pinfunction "9_9") (pintype "passive+no_connect"))
    )
  )
)
